# I2C_EEPROM.net
KiCad netlist of a schematic drawn in Altium Designer
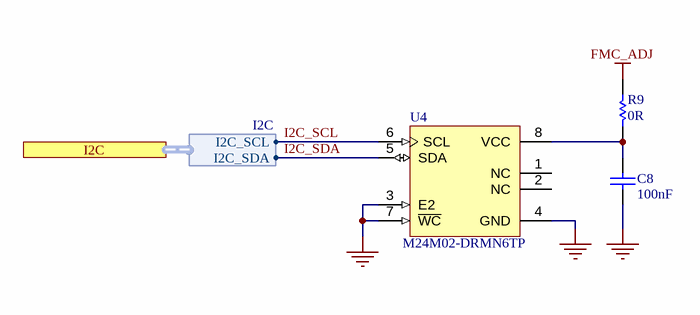
[diagram p0: I2C_EEPROM.SchDoc]

(export (version "E")
  (design (tool "Eeschema 10.0.6"))
  (components
    (comp (ref "C8")
      (value "100nF")
      (footprint "CAPC1050X55X23LL05T13")
      (description "Chip Capacitor, 100 nF, +/- 10%, 16 V, -55 to 125 degC, 0402 (1005 Metric), RoHS, Tape and Reel")
      (fields
        (field (name "MANUFACTURER") "Samsung Electro-Mechanics")
        (field (name "MANUFACTURER PART NUMBER") "CL05B104KO5NNNC")
      )
      (libsource (lib "Altium Content Vault") (part "CAP-NP-2"))
    )
    (comp (ref "R9")
      (value "0R")
      (footprint "RESC1005X40X25LL05T10")
      (fields
        (field (name "MANUFACTURER") "Yageo")
        (field (name "PART NUMBER") "RC0402JR-070RL")
        (field (name "TOLERANCE") "5%")
      )
      (libsource (lib "Altium Content Vault") (part "RES"))
    )
    (comp (ref "U4")
      (value "M24M02-DRMN6TP")
      (footprint "M08A_N")
      (description "IC EEPROM 2MBIT 1MHZ 8SO")
      (fields (field (name "MANUFACTURER") "STMicroelectronics"))
      (libsource (lib "ETHZ Vault") (part "CMP-00477-1"))
    )
  )
  (nets
    (net (code "2") (name "/I2C_SCL") (class "Default")
      (node (ref "U4") (pin "6") (pinfunction "SCL_6") (pintype "input"))
    )
    (net (code "3") (name "/I2C_SDA") (class "Default")
      (node (ref "U4") (pin "5") (pinfunction "SDA_5") (pintype "bidirectional"))
    )
    (net (code "5") (name "FMC_ADJ") (class "Default")
      (node (ref "R9") (pin "2") (pinfunction "2_2") (pintype "passive"))
    )
    (net (code "6") (name "GND") (class "Default")
      (node (ref "C8") (pin "1") (pinfunction "1_1") (pintype "passive"))
      (node (ref "U4") (pin "3") (pinfunction "E2_3") (pintype "input"))
      (node (ref "U4") (pin "4") (pinfunction "GND_4") (pintype "power_in"))
      (node (ref "U4") (pin "7") (pinfunction "~{WC}_7") (pintype "input"))
    )
    (net (code "7") (name "Net-(U4-VCC)") (class "Default")
      (node (ref "C8") (pin "2") (pinfunction "2_2") (pintype "passive"))
      (node (ref "R9") (pin "1") (pinfunction "1_1") (pintype "passive"))
      (node (ref "U4") (pin "8") (pinfunction "VCC_8") (pintype "power_in"))
    )
    (net (code "8") (name "unconnected-(U4-NC-Pad1)") (class "Default")
      (node (ref "U4") (pin "1") (pinfunction "NC_1") (pintype "passive"))
    )
    (net (code "9") (name "unconnected-(U4-NC-Pad2)") (class "Default")
      (node (ref "U4") (pin "2") (pinfunction "NC_2") (pintype "passive"))
    )
  )
)
